# Interface.net
KiCad netlist of a schematic drawn in Altium Designer
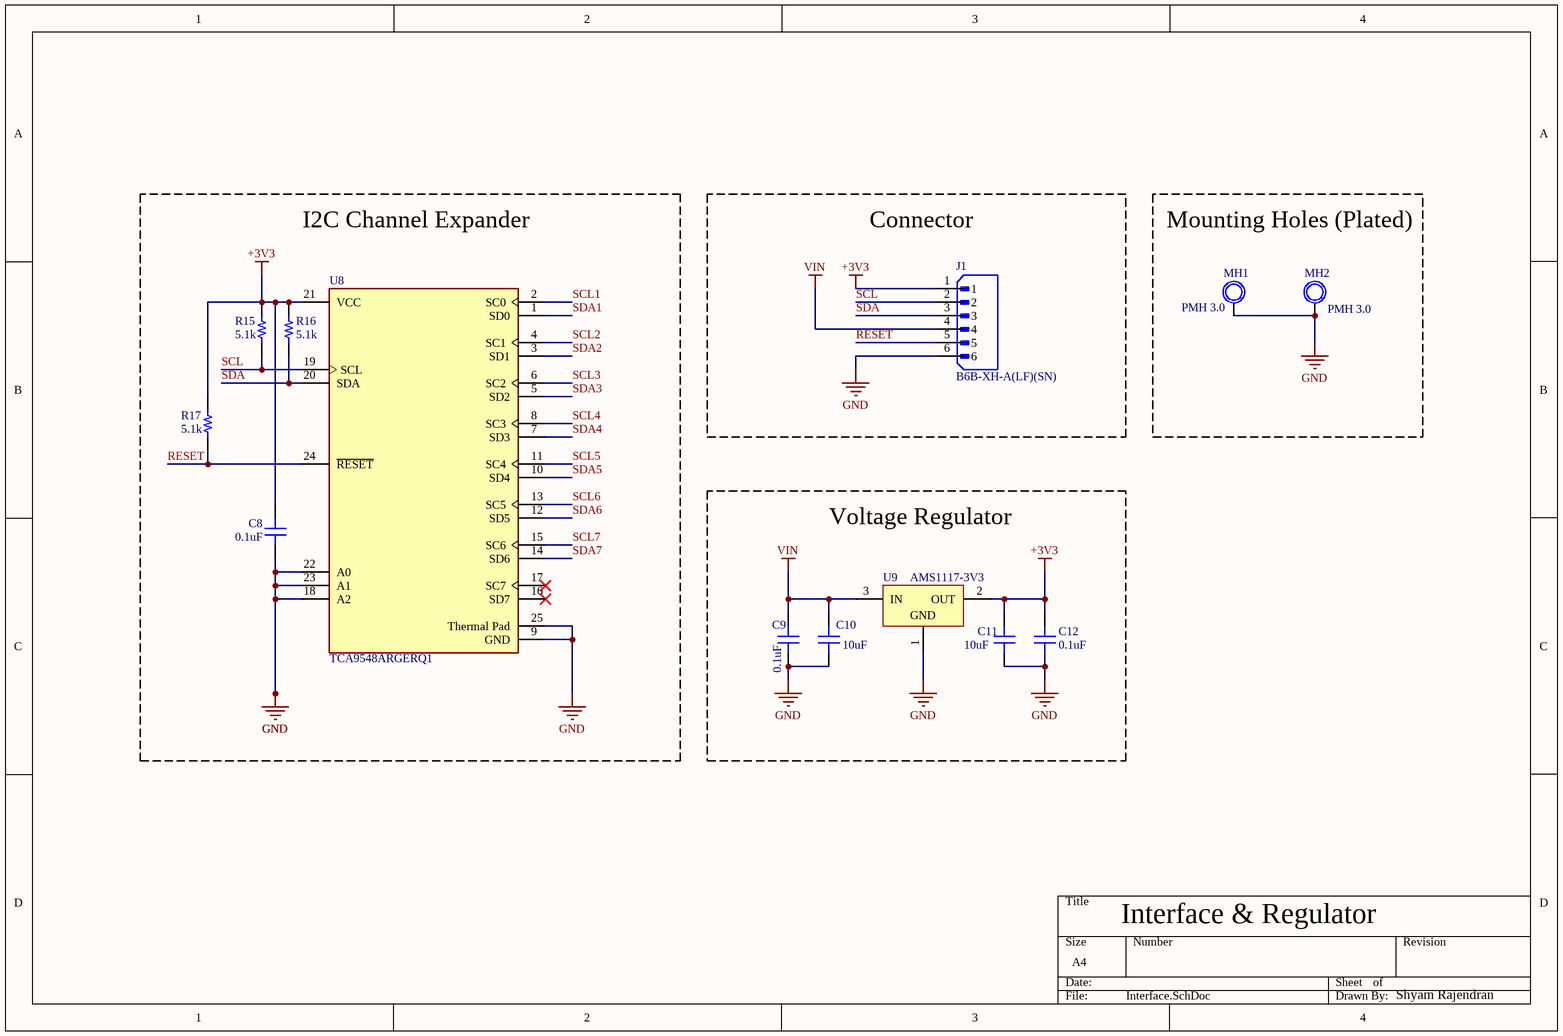
[diagram p0: Interface.SchDoc]

(export (version "E")
  (design (tool "Eeschema 10.0.6"))
  (components
    (comp (ref "C8")
      (value "10uF")
      (footprint "CAP 0603_1608")
      (description "0603")
      (fields
        (field (name "PART NUMBER") "GCJ188C70J335KE02D")
        (field (name "CAPACITANCE") "0.1uF")
        (field (name "MANUFACTURER") "Murata Electronics")
      )
      (libsource (lib "Celestial Altium Library - altium_library") (part "Capacitor"))
    )
    (comp (ref "C9")
      (value "10uF")
      (footprint "CAP 0603_1608")
      (description "0603")
      (fields
        (field (name "PART NUMBER") "GCJ188C70J335KE02D")
        (field (name "CAPACITANCE") "0.1uF")
        (field (name "MANUFACTURER") "Murata Electronics")
      )
      (libsource (lib "Celestial Altium Library - altium_library") (part "Capacitor"))
    )
    (comp (ref "C10")
      (value "10uF")
      (footprint "CAP 0603_1608")
      (description "0603")
      (fields
        (field (name "PART NUMBER") "GCJ188C70J335KE02D")
        (field (name "CAPACITANCE") "10uF")
        (field (name "MANUFACTURER") "Murata Electronics")
      )
      (libsource (lib "Celestial Altium Library - altium_library") (part "Capacitor"))
    )
    (comp (ref "C11")
      (value "10uF")
      (footprint "CAP 0603_1608")
      (description "0603")
      (fields
        (field (name "PART NUMBER") "GCJ188C70J335KE02D")
        (field (name "CAPACITANCE") "10uF")
        (field (name "MANUFACTURER") "Murata Electronics")
      )
      (libsource (lib "Celestial Altium Library - altium_library") (part "Capacitor"))
    )
    (comp (ref "C12")
      (value "10uF")
      (footprint "CAP 0603_1608")
      (description "0603")
      (fields
        (field (name "PART NUMBER") "GCJ188C70J335KE02D")
        (field (name "CAPACITANCE") "0.1uF")
        (field (name "MANUFACTURER") "Murata Electronics")
      )
      (libsource (lib "Celestial Altium Library - altium_library") (part "Capacitor"))
    )
    (comp (ref "J1")
      (value "B6B-XH-A(LF)(SN)")
      (footprint "JST_B6B-XH-A(LF)(SN)")
      (description "Connector Header Through Hole 6 position 0.098 (2.50mm)")
      (fields (field (name "MF") "JST Sales"))
      (libsource (lib "Schlib1") (part "B6B-XH-A(LF)(SN)"))
    )
    (comp (ref "MH1")
      (value "PMH 3.0")
      (footprint "NPMH")
      (description "PMH 3.0mm")
      (libsource (lib "Schlib1") (part "PMH"))
    )
    (comp (ref "MH2")
      (value "PMH 3.0")
      (footprint "NPMH")
      (description "PMH 3.0mm")
      (libsource (lib "Schlib1") (part "PMH"))
    )
    (comp (ref "R15")
      (value "5.1k")
      (footprint "RES 0603_1608")
      (description "0603")
      (fields
        (field (name "PART NUMBER") "RNCS0603BKE10K0")
        (field (name "MANUFACTURER") "Stackpole Electronics Inc")
      )
      (libsource (lib "Celestial Altium Library - altium_library") (part "Resistor"))
    )
    (comp (ref "R16")
      (value "5.1k")
      (footprint "RES 0603_1608")
      (description "0603")
      (fields
        (field (name "PART NUMBER") "RNCS0603BKE10K0")
        (field (name "MANUFACTURER") "Stackpole Electronics Inc")
      )
      (libsource (lib "Celestial Altium Library - altium_library") (part "Resistor"))
    )
    (comp (ref "R17")
      (value "5.1k")
      (footprint "RES 0603_1608")
      (description "0603")
      (fields
        (field (name "PART NUMBER") "RNCS0603BKE10K0")
        (field (name "MANUFACTURER") "Stackpole Electronics Inc")
      )
      (libsource (lib "Celestial Altium Library - altium_library") (part "Resistor"))
    )
    (comp (ref "U8")
      (value "TCA9548ARGERQ1")
      (footprint "TCA9548")
      (description "I2C Switch with Reset 8 Channel Bi-Directional 1.65V to 5.25V 24-Pin VQFN Cut Tape")
      (libsource (lib "Schlib1") (part "TCA9548ARGERQ1"))
    )
    (comp (ref "U9")
      (value "AMS1117-3V3")
      (footprint "AMS1117, 5V")
      (description "SOT89")
      (libsource (lib "Schlib1") (part "AMS1117-3V3"))
    )
  )
  (nets
    (net (code "1") (name "+3V3") (class "Default")
      (node (ref "C11") (pin "2") (pinfunction "2_2") (pintype "passive"))
      (node (ref "C12") (pin "2") (pinfunction "2_2") (pintype "passive"))
      (node (ref "C8") (pin "2") (pinfunction "2_2") (pintype "passive"))
      (node (ref "J1") (pin "1") (pinfunction "1_1") (pintype "passive"))
      (node (ref "R15") (pin "2") (pinfunction "2_2") (pintype "passive"))
      (node (ref "R16") (pin "2") (pinfunction "2_2") (pintype "passive"))
      (node (ref "R17") (pin "2") (pinfunction "2_2") (pintype "passive"))
      (node (ref "U8") (pin "21") (pinfunction "VCC_21") (pintype "passive"))
      (node (ref "U9") (pin "2") (pinfunction "OUT_2") (pintype "power_in"))
    )
    (net (code "2") (name "/RESET") (class "Default")
      (node (ref "J1") (pin "5") (pinfunction "5_5") (pintype "passive"))
      (node (ref "R17") (pin "1") (pinfunction "1_1") (pintype "passive"))
      (node (ref "U8") (pin "24") (pinfunction "~{RESET}_24") (pintype "passive"))
    )
    (net (code "3") (name "/SCL") (class "Default")
      (node (ref "J1") (pin "2") (pinfunction "2_2") (pintype "passive"))
      (node (ref "R15") (pin "1") (pinfunction "1_1") (pintype "passive"))
      (node (ref "U8") (pin "19") (pinfunction "SCL_19") (pintype "passive"))
    )
    (net (code "4") (name "/SCL1") (class "Default")
      (node (ref "U8") (pin "2") (pinfunction "SC0_2") (pintype "passive"))
    )
    (net (code "5") (name "/SCL2") (class "Default")
      (node (ref "U8") (pin "4") (pinfunction "SC1_4") (pintype "passive"))
    )
    (net (code "6") (name "/SCL3") (class "Default")
      (node (ref "U8") (pin "6") (pinfunction "SC2_6") (pintype "passive"))
    )
    (net (code "7") (name "/SCL4") (class "Default")
      (node (ref "U8") (pin "8") (pinfunction "SC3_8") (pintype "passive"))
    )
    (net (code "8") (name "/SCL5") (class "Default")
      (node (ref "U8") (pin "11") (pinfunction "SC4_11") (pintype "passive"))
    )
    (net (code "9") (name "/SCL6") (class "Default")
      (node (ref "U8") (pin "13") (pinfunction "SC5_13") (pintype "passive"))
    )
    (net (code "10") (name "/SCL7") (class "Default")
      (node (ref "U8") (pin "15") (pinfunction "SC6_15") (pintype "passive"))
    )
    (net (code "11") (name "/SDA") (class "Default")
      (node (ref "J1") (pin "3") (pinfunction "3_3") (pintype "passive"))
      (node (ref "R16") (pin "1") (pinfunction "1_1") (pintype "passive"))
      (node (ref "U8") (pin "20") (pinfunction "SDA_20") (pintype "passive"))
    )
    (net (code "12") (name "/SDA1") (class "Default")
      (node (ref "U8") (pin "1") (pinfunction "SD0_1") (pintype "passive"))
    )
    (net (code "13") (name "/SDA2") (class "Default")
      (node (ref "U8") (pin "3") (pinfunction "SD1_3") (pintype "passive"))
    )
    (net (code "14") (name "/SDA3") (class "Default")
      (node (ref "U8") (pin "5") (pinfunction "SD2_5") (pintype "passive"))
    )
    (net (code "15") (name "/SDA4") (class "Default")
      (node (ref "U8") (pin "7") (pinfunction "SD3_7") (pintype "passive"))
    )
    (net (code "16") (name "/SDA5") (class "Default")
      (node (ref "U8") (pin "10") (pinfunction "SD4_10") (pintype "passive"))
    )
    (net (code "17") (name "/SDA6") (class "Default")
      (node (ref "U8") (pin "12") (pinfunction "SD5_12") (pintype "passive"))
    )
    (net (code "18") (name "/SDA7") (class "Default")
      (node (ref "U8") (pin "14") (pinfunction "SD6_14") (pintype "passive"))
    )
    (net (code "19") (name "GND") (class "Default")
      (node (ref "C10") (pin "1") (pinfunction "1_1") (pintype "passive"))
      (node (ref "C11") (pin "1") (pinfunction "1_1") (pintype "passive"))
      (node (ref "C12") (pin "1") (pinfunction "1_1") (pintype "passive"))
      (node (ref "C8") (pin "1") (pinfunction "1_1") (pintype "passive"))
      (node (ref "C9") (pin "1") (pinfunction "1_1") (pintype "passive"))
      (node (ref "J1") (pin "6") (pinfunction "6_6") (pintype "passive"))
      (node (ref "MH1") (pin "GND") (pinfunction "GND_GND") (pintype "passive"))
      (node (ref "MH2") (pin "GND") (pinfunction "GND_GND") (pintype "passive"))
      (node (ref "U8") (pin "18") (pinfunction "A2_18") (pintype "passive"))
      (node (ref "U8") (pin "22") (pinfunction "A0_22") (pintype "passive"))
      (node (ref "U8") (pin "23") (pinfunction "A1_23") (pintype "passive"))
      (node (ref "U8") (pin "25") (pinfunction "Thermal_Pad_25") (pintype "passive"))
      (node (ref "U8") (pin "9") (pinfunction "GND_9") (pintype "passive"))
      (node (ref "U9") (pin "1") (pinfunction "GND_1") (pintype "power_in"))
    )
    (net (code "20") (name "VIN") (class "Default")
      (node (ref "C10") (pin "2") (pinfunction "2_2") (pintype "passive"))
      (node (ref "C9") (pin "2") (pinfunction "2_2") (pintype "passive"))
      (node (ref "J1") (pin "4") (pinfunction "4_4") (pintype "passive"))
      (node (ref "U9") (pin "3") (pinfunction "IN_3") (pintype "power_in"))
    )
    (net (code "21") (name "unconnected-(U8-SC7-Pad17)") (class "Default")
      (node (ref "U8") (pin "17") (pinfunction "SC7_17") (pintype "passive+no_connect"))
    )
    (net (code "22") (name "unconnected-(U8-SD7-Pad16)") (class "Default")
      (node (ref "U8") (pin "16") (pinfunction "SD7_16") (pintype "passive+no_connect"))
    )
  )
)
